# BigBrdSL.net
KiCad netlist of a schematic drawn in EAGLE
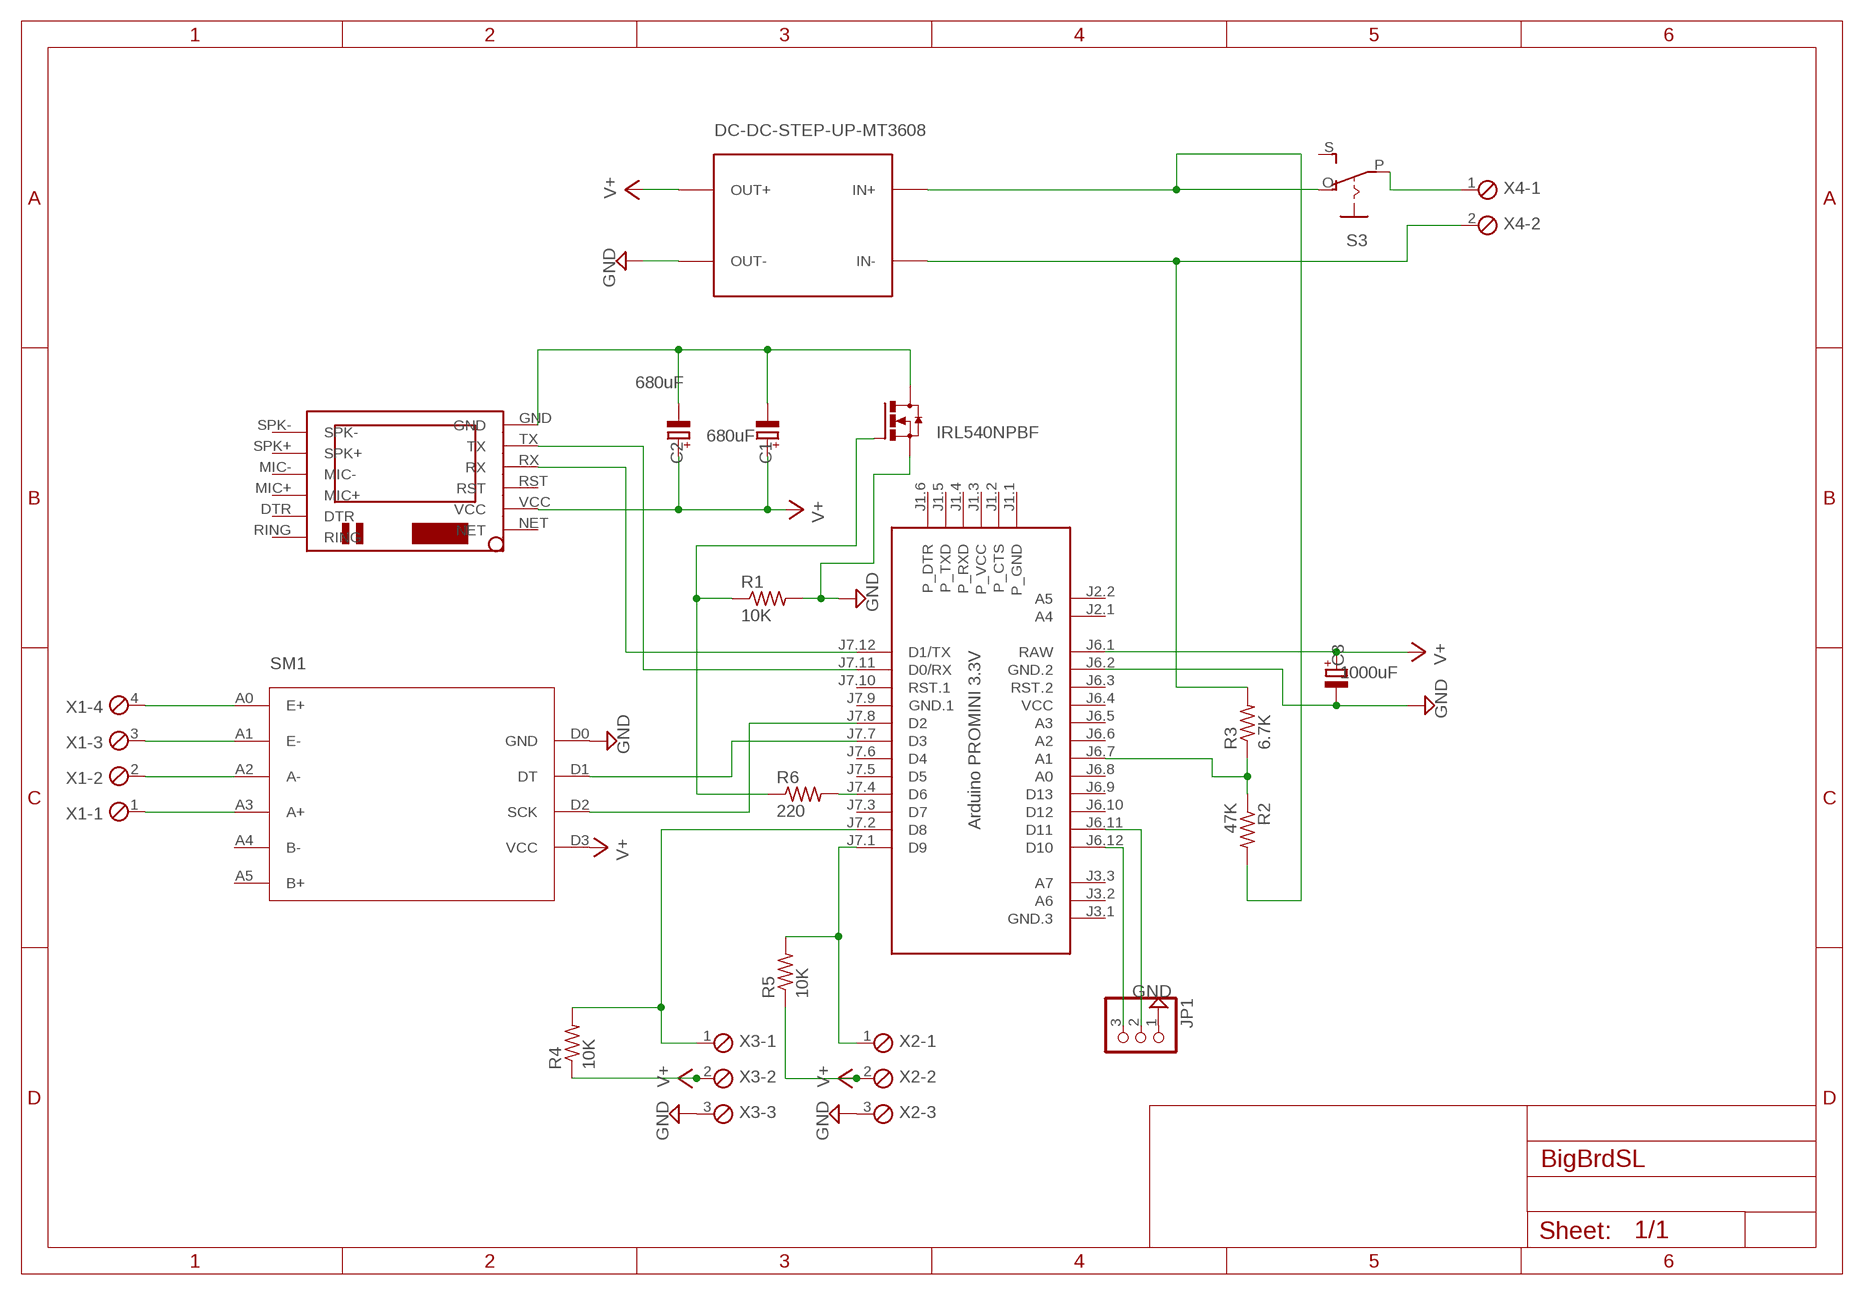
[diagram p0: schematic, sheet 1]

(export (version "E")
  (design (tool "Eeschema 10.0.6"))
  (components
    (comp (ref "C1")
      (value "680uF")
      (footprint "eagle-import:E3,5-8")
      (libsource (lib "eagle-import") (part "CPOL-EUE3.5-8"))
    )
    (comp (ref "C2")
      (value "680uF")
      (footprint "eagle-import:E3,5-8")
      (libsource (lib "eagle-import") (part "CPOL-EUE3.5-8"))
    )
    (comp (ref "C3")
      (value "1000uF")
      (footprint "eagle-import:E3,5-8")
      (libsource (lib "eagle-import") (part "CPOL-EUE3.5-8"))
    )
    (comp (ref "IRL540NPBF")
      (value "IRF520NPBF")
      (footprint "eagle-import:TO-220")
      (fields
        (field (name "DIGIKEY_PART_NUMBER") "IRF520NPBF-ND")
        (field (name "MANUFACTURER") "Infineon Technologies")
        (field (name "DIGIKEY_PART_NUMBER_1") "IRlL540NPBF")
        (field (name "MPN") "IRL540NPBF")
        (field (name "CREATED_BY") "PCBLayout.com")
      )
      (libsource (lib "eagle-import") (part "IRF520NPBF"))
    )
    (comp (ref "JP1")
      (value "PINHD-1X3")
      (footprint "eagle-import:1X03")
      (libsource (lib "eagle-import") (part "PINHD-1X3"))
    )
    (comp (ref "M1")
      (value "ARDUINO-PRO-MINI-5.0V")
      (footprint "eagle-import:ARDUINO-PRO-MINI")
      (libsource (lib "eagle-import") (part "ARDUINO-PRO-MINI-5.0V"))
    )
    (comp (ref "MT36-08")
      (value "DC-DC-STEP-UP-MT3608")
      (footprint "eagle-import:DC-DC-STEP-UP-MT3608")
      (libsource (lib "eagle-import") (part "DC-DC-STEP-UP-MT3608"))
    )
    (comp (ref "R1")
      (value "10K")
      (footprint "eagle-import:0207_7")
      (libsource (lib "eagle-import") (part "R-US_0207/7"))
    )
    (comp (ref "R2")
      (value "47K")
      (footprint "eagle-import:0207_7")
      (libsource (lib "eagle-import") (part "R-US_0207/7"))
    )
    (comp (ref "R3")
      (value "6.7K")
      (footprint "eagle-import:0207_7")
      (libsource (lib "eagle-import") (part "R-US_0207/7"))
    )
    (comp (ref "R4")
      (value "10K")
      (footprint "eagle-import:0207_7")
      (libsource (lib "eagle-import") (part "R-US_0207/7"))
    )
    (comp (ref "R5")
      (value "10K")
      (footprint "eagle-import:0207_7")
      (libsource (lib "eagle-import") (part "R-US_0207/7"))
    )
    (comp (ref "R6")
      (value "220")
      (footprint "eagle-import:0207_7")
      (libsource (lib "eagle-import") (part "R-US_0207/7"))
    )
    (comp (ref "S3")
      (value "EG1218S")
      (footprint "eagle-import:EG1218")
      (libsource (lib "eagle-import") (part "EG1218S"))
    )
    (comp (ref "SM1")
      (value "HX711")
      (footprint "eagle-import:HX711")
      (libsource (lib "eagle-import") (part "HX711"))
    )
    (comp (ref "U$3")
      (value "SIM800LMODULE")
      (footprint "eagle-import:SIM800LMODULE")
      (libsource (lib "eagle-import") (part "SIM800LMODULE"))
    )
    (comp (ref "X1")
      (value "MPT4")
      (footprint "eagle-import:4POL254")
      (libsource (lib "eagle-import") (part "MPT4"))
    )
    (comp (ref "X2")
      (value "MPT3")
      (footprint "eagle-import:3POL254")
      (libsource (lib "eagle-import") (part "MPT3"))
    )
    (comp (ref "X3")
      (value "MPT3")
      (footprint "eagle-import:3POL254")
      (libsource (lib "eagle-import") (part "MPT3"))
    )
    (comp (ref "X4")
      (value "MPT2")
      (footprint "eagle-import:2POL254")
      (libsource (lib "eagle-import") (part "MPT2"))
    )
  )
  (nets
    (net (code "1") (name "/GND.1") (class "Default")
      (node (ref "M1") (pin "J7.9") (pinfunction "GND.1_J7.9") (pintype "power_in"))
    )
    (net (code "2") (name "/VCC") (class "Default")
      (node (ref "M1") (pin "J6.4") (pinfunction "VCC_J6.4") (pintype "power_in"))
    )
    (net (code "3") (name "GND") (class "Default")
      (node (ref "C3") (pin "-") (pinfunction "-_-") (pintype "passive"))
      (node (ref "IRL540NPBF") (pin "S") (pinfunction "S_S") (pintype "passive"))
      (node (ref "JP1") (pin "1") (pinfunction "1_1") (pintype "passive"))
      (node (ref "M1") (pin "J6.2") (pinfunction "GND.2_J6.2") (pintype "power_in"))
      (node (ref "MT36-08") (pin "OUT-") (pinfunction "OUT-_OUT-") (pintype "bidirectional"))
      (node (ref "R1") (pin "2") (pinfunction "2_2") (pintype "passive"))
      (node (ref "SM1") (pin "D0") (pinfunction "GND_D0") (pintype "bidirectional"))
      (node (ref "X2") (pin "3") (pinfunction "1_3") (pintype "passive"))
      (node (ref "X3") (pin "3") (pinfunction "1_3") (pintype "passive"))
    )
    (net (code "4") (name "Net-(C1-Pad-)") (class "Default")
      (node (ref "C1") (pin "-") (pinfunction "-_-") (pintype "passive"))
      (node (ref "C2") (pin "-") (pinfunction "-_-") (pintype "passive"))
      (node (ref "IRL540NPBF") (pin "D") (pinfunction "D_D") (pintype "passive"))
      (node (ref "U$3") (pin "GND") (pinfunction "GND_GND") (pintype "bidirectional"))
    )
    (net (code "5") (name "Net-(IRL540NPBF-PadG)") (class "Default")
      (node (ref "IRL540NPBF") (pin "G") (pinfunction "G_G") (pintype "passive"))
      (node (ref "R1") (pin "1") (pinfunction "1_1") (pintype "passive"))
      (node (ref "R6") (pin "1") (pinfunction "1_1") (pintype "passive"))
    )
    (net (code "6") (name "Net-(M1-A1)") (class "Default")
      (node (ref "M1") (pin "J6.7") (pinfunction "A1_J6.7") (pintype "bidirectional"))
      (node (ref "R2") (pin "1") (pinfunction "1_1") (pintype "passive"))
      (node (ref "R3") (pin "1") (pinfunction "1_1") (pintype "passive"))
    )
    (net (code "7") (name "Net-(M1-D0{slash}RX)") (class "Default")
      (node (ref "M1") (pin "J7.11") (pinfunction "D0/RX_J7.11") (pintype "bidirectional"))
      (node (ref "U$3") (pin "TX") (pinfunction "TX_TX") (pintype "bidirectional"))
    )
    (net (code "8") (name "Net-(M1-D1{slash}TX)") (class "Default")
      (node (ref "M1") (pin "J7.12") (pinfunction "D1/TX_J7.12") (pintype "bidirectional"))
      (node (ref "U$3") (pin "RX") (pinfunction "RX_RX") (pintype "bidirectional"))
    )
    (net (code "9") (name "Net-(M1-D2)") (class "Default")
      (node (ref "M1") (pin "J7.8") (pinfunction "D2_J7.8") (pintype "bidirectional"))
      (node (ref "SM1") (pin "D2") (pinfunction "SCK_D2") (pintype "bidirectional"))
    )
    (net (code "10") (name "Net-(M1-D3)") (class "Default")
      (node (ref "M1") (pin "J7.7") (pinfunction "D3_J7.7") (pintype "bidirectional"))
      (node (ref "SM1") (pin "D1") (pinfunction "DT_D1") (pintype "bidirectional"))
    )
    (net (code "11") (name "Net-(M1-D6)") (class "Default")
      (node (ref "M1") (pin "J7.4") (pinfunction "D6_J7.4") (pintype "bidirectional"))
      (node (ref "R6") (pin "2") (pinfunction "2_2") (pintype "passive"))
    )
    (net (code "12") (name "Net-(M1-D8)") (class "Default")
      (node (ref "M1") (pin "J7.2") (pinfunction "D8_J7.2") (pintype "bidirectional"))
      (node (ref "R4") (pin "2") (pinfunction "2_2") (pintype "passive"))
      (node (ref "X3") (pin "1") (pinfunction "1_1") (pintype "passive"))
    )
    (net (code "13") (name "Net-(M1-D9)") (class "Default")
      (node (ref "M1") (pin "J7.1") (pinfunction "D9_J7.1") (pintype "bidirectional"))
      (node (ref "R5") (pin "2") (pinfunction "2_2") (pintype "passive"))
      (node (ref "X2") (pin "1") (pinfunction "1_1") (pintype "passive"))
    )
    (net (code "14") (name "Net-(M1-D10)") (class "Default")
      (node (ref "JP1") (pin "3") (pinfunction "3_3") (pintype "passive"))
      (node (ref "M1") (pin "J6.12") (pinfunction "D10_J6.12") (pintype "bidirectional"))
    )
    (net (code "15") (name "Net-(M1-D11)") (class "Default")
      (node (ref "JP1") (pin "2") (pinfunction "2_2") (pintype "passive"))
      (node (ref "M1") (pin "J6.11") (pinfunction "D11_J6.11") (pintype "bidirectional"))
    )
    (net (code "16") (name "Net-(MT36-08-PadIN+)") (class "Default")
      (node (ref "MT36-08") (pin "IN+") (pinfunction "IN+_IN+") (pintype "bidirectional"))
      (node (ref "R2") (pin "2") (pinfunction "2_2") (pintype "passive"))
      (node (ref "S3") (pin "O") (pinfunction "O_O") (pintype "passive"))
    )
    (net (code "17") (name "Net-(S3-PadP)") (class "Default")
      (node (ref "S3") (pin "P") (pinfunction "P_P") (pintype "passive"))
      (node (ref "X4") (pin "1") (pinfunction "1_1") (pintype "passive"))
    )
    (net (code "18") (name "Net-(SM1-A+)") (class "Default")
      (node (ref "SM1") (pin "A3") (pinfunction "A+_A3") (pintype "bidirectional"))
      (node (ref "X1") (pin "1") (pinfunction "1_1") (pintype "passive"))
    )
    (net (code "19") (name "Net-(SM1-A-)") (class "Default")
      (node (ref "SM1") (pin "A2") (pinfunction "A-_A2") (pintype "bidirectional"))
      (node (ref "X1") (pin "2") (pinfunction "1_2") (pintype "passive"))
    )
    (net (code "20") (name "Net-(SM1-E+)") (class "Default")
      (node (ref "SM1") (pin "A0") (pinfunction "E+_A0") (pintype "bidirectional"))
      (node (ref "X1") (pin "4") (pinfunction "1_4") (pintype "passive"))
    )
    (net (code "21") (name "Net-(SM1-E-)") (class "Default")
      (node (ref "SM1") (pin "A1") (pinfunction "E-_A1") (pintype "bidirectional"))
      (node (ref "X1") (pin "3") (pinfunction "1_3") (pintype "passive"))
    )
    (net (code "22") (name "Net-(X4B-1)") (class "Default")
      (node (ref "MT36-08") (pin "IN-") (pinfunction "IN-_IN-") (pintype "bidirectional"))
      (node (ref "R3") (pin "2") (pinfunction "2_2") (pintype "passive"))
      (node (ref "X4") (pin "2") (pinfunction "1_2") (pintype "passive"))
    )
    (net (code "23") (name "V+") (class "Default")
      (node (ref "C1") (pin "+") (pinfunction "+_+") (pintype "passive"))
      (node (ref "C2") (pin "+") (pinfunction "+_+") (pintype "passive"))
      (node (ref "C3") (pin "+") (pinfunction "+_+") (pintype "passive"))
      (node (ref "M1") (pin "J6.1") (pinfunction "RAW_J6.1") (pintype "power_in"))
      (node (ref "MT36-08") (pin "OUT+") (pinfunction "OUT+_OUT+") (pintype "bidirectional"))
      (node (ref "R4") (pin "1") (pinfunction "1_1") (pintype "passive"))
      (node (ref "R5") (pin "1") (pinfunction "1_1") (pintype "passive"))
      (node (ref "SM1") (pin "D3") (pinfunction "VCC_D3") (pintype "bidirectional"))
      (node (ref "U$3") (pin "VCC") (pinfunction "VCC_VCC") (pintype "bidirectional"))
      (node (ref "X2") (pin "2") (pinfunction "1_2") (pintype "passive"))
      (node (ref "X3") (pin "2") (pinfunction "1_2") (pintype "passive"))
    )
    (net (code "24") (name "unconnected-(M1-A0-PadJ6.8)") (class "Default")
      (node (ref "M1") (pin "J6.8") (pinfunction "A0_J6.8") (pintype "bidirectional"))
    )
    (net (code "25") (name "unconnected-(M1-A2-PadJ6.6)") (class "Default")
      (node (ref "M1") (pin "J6.6") (pinfunction "A2_J6.6") (pintype "bidirectional"))
    )
    (net (code "26") (name "unconnected-(M1-A3-PadJ6.5)") (class "Default")
      (node (ref "M1") (pin "J6.5") (pinfunction "A3_J6.5") (pintype "bidirectional"))
    )
    (net (code "27") (name "unconnected-(M1-A4-PadJ2.1)") (class "Default")
      (node (ref "M1") (pin "J2.1") (pinfunction "A4_J2.1") (pintype "bidirectional"))
    )
    (net (code "28") (name "unconnected-(M1-A5-PadJ2.2)") (class "Default")
      (node (ref "M1") (pin "J2.2") (pinfunction "A5_J2.2") (pintype "bidirectional"))
    )
    (net (code "29") (name "unconnected-(M1-A6-PadJ3.2)") (class "Default")
      (node (ref "M1") (pin "J3.2") (pinfunction "A6_J3.2") (pintype "bidirectional"))
    )
    (net (code "30") (name "unconnected-(M1-A7-PadJ3.3)") (class "Default")
      (node (ref "M1") (pin "J3.3") (pinfunction "A7_J3.3") (pintype "bidirectional"))
    )
    (net (code "31") (name "unconnected-(M1-D4-PadJ7.6)") (class "Default")
      (node (ref "M1") (pin "J7.6") (pinfunction "D4_J7.6") (pintype "bidirectional"))
    )
    (net (code "32") (name "unconnected-(M1-D5-PadJ7.5)") (class "Default")
      (node (ref "M1") (pin "J7.5") (pinfunction "D5_J7.5") (pintype "bidirectional"))
    )
    (net (code "33") (name "unconnected-(M1-D7-PadJ7.3)") (class "Default")
      (node (ref "M1") (pin "J7.3") (pinfunction "D7_J7.3") (pintype "bidirectional"))
    )
    (net (code "34") (name "unconnected-(M1-D12-PadJ6.10)") (class "Default")
      (node (ref "M1") (pin "J6.10") (pinfunction "D12_J6.10") (pintype "bidirectional"))
    )
    (net (code "35") (name "unconnected-(M1-D13-PadJ6.9)") (class "Default")
      (node (ref "M1") (pin "J6.9") (pinfunction "D13_J6.9") (pintype "bidirectional"))
    )
    (net (code "36") (name "unconnected-(M1-GND.3-PadJ3.1)") (class "Default")
      (node (ref "M1") (pin "J3.1") (pinfunction "GND.3_J3.1") (pintype "bidirectional"))
    )
    (net (code "37") (name "unconnected-(M1-P_CTS-PadJ1.2)") (class "Default")
      (node (ref "M1") (pin "J1.2") (pinfunction "P_CTS_J1.2") (pintype "bidirectional"))
    )
    (net (code "38") (name "unconnected-(M1-P_DTR-PadJ1.6)") (class "Default")
      (node (ref "M1") (pin "J1.6") (pinfunction "P_DTR_J1.6") (pintype "bidirectional"))
    )
    (net (code "39") (name "unconnected-(M1-P_GND-PadJ1.1)") (class "Default")
      (node (ref "M1") (pin "J1.1") (pinfunction "P_GND_J1.1") (pintype "bidirectional"))
    )
    (net (code "40") (name "unconnected-(M1-P_RXD-PadJ1.4)") (class "Default")
      (node (ref "M1") (pin "J1.4") (pinfunction "P_RXD_J1.4") (pintype "bidirectional"))
    )
    (net (code "41") (name "unconnected-(M1-P_TXD-PadJ1.5)") (class "Default")
      (node (ref "M1") (pin "J1.5") (pinfunction "P_TXD_J1.5") (pintype "bidirectional"))
    )
    (net (code "42") (name "unconnected-(M1-P_VCC-PadJ1.3)") (class "Default")
      (node (ref "M1") (pin "J1.3") (pinfunction "P_VCC_J1.3") (pintype "bidirectional"))
    )
    (net (code "43") (name "unconnected-(M1-RST.1-PadJ7.10)") (class "Default")
      (node (ref "M1") (pin "J7.10") (pinfunction "RST.1_J7.10") (pintype "bidirectional"))
    )
    (net (code "44") (name "unconnected-(M1-RST.2-PadJ6.3)") (class "Default")
      (node (ref "M1") (pin "J6.3") (pinfunction "RST.2_J6.3") (pintype "bidirectional"))
    )
    (net (code "45") (name "unconnected-(S3-PadS)") (class "Default")
      (node (ref "S3") (pin "S") (pinfunction "S_S") (pintype "passive"))
    )
    (net (code "46") (name "unconnected-(SM1-B+-PadA5)") (class "Default")
      (node (ref "SM1") (pin "A5") (pinfunction "B+_A5") (pintype "bidirectional"))
    )
    (net (code "47") (name "unconnected-(SM1-B--PadA4)") (class "Default")
      (node (ref "SM1") (pin "A4") (pinfunction "B-_A4") (pintype "bidirectional"))
    )
    (net (code "48") (name "unconnected-(U$3-PadDTR)") (class "Default")
      (node (ref "U$3") (pin "DTR") (pinfunction "DTR_DTR") (pintype "bidirectional"))
    )
    (net (code "49") (name "unconnected-(U$3-PadMIC+)") (class "Default")
      (node (ref "U$3") (pin "MIC+") (pinfunction "MIC+_MIC+") (pintype "bidirectional"))
    )
    (net (code "50") (name "unconnected-(U$3-PadMIC-)") (class "Default")
      (node (ref "U$3") (pin "MIC-") (pinfunction "MIC-_MIC-") (pintype "bidirectional"))
    )
    (net (code "51") (name "unconnected-(U$3-PadNET)") (class "Default")
      (node (ref "U$3") (pin "NET") (pinfunction "NET_NET") (pintype "bidirectional"))
    )
    (net (code "52") (name "unconnected-(U$3-PadRING)") (class "Default")
      (node (ref "U$3") (pin "RING") (pinfunction "RING_RING") (pintype "bidirectional"))
    )
    (net (code "53") (name "unconnected-(U$3-PadRST)") (class "Default")
      (node (ref "U$3") (pin "RST") (pinfunction "RST_RST") (pintype "bidirectional"))
    )
    (net (code "54") (name "unconnected-(U$3-PadSPK+)") (class "Default")
      (node (ref "U$3") (pin "SPK+") (pinfunction "SPK+_SPK+") (pintype "bidirectional"))
    )
    (net (code "55") (name "unconnected-(U$3-PadSPK-)") (class "Default")
      (node (ref "U$3") (pin "SPK-") (pinfunction "SPK-_SPK-") (pintype "bidirectional"))
    )
  )
)
